# untitled.net
KiCad netlist of a schematic drawn in EAGLE
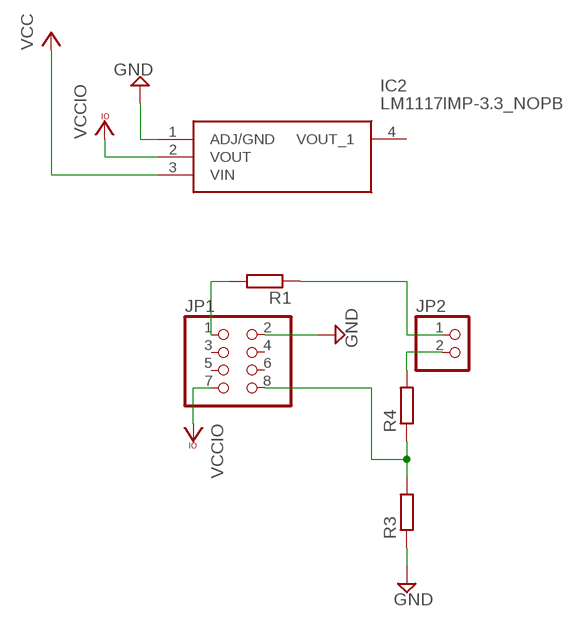
[diagram p0: schematic, sheet 1]

(export (version "E")
  (design (tool "Eeschema 10.0.6"))
  (components
    (comp (ref "IC2")
      (value "LM1117IMP-3.3_NOPB")
      (footprint "eagle-import:SOT230P700X180-4N")
      (fields
        (field (name "MANUFACTURER_PART_NUMBER") "LM1117IMP-3.3/NOPB")
        (field (name "MOUSER_PART_NUMBER") "926-LM1117IMP3.3NOPB")
        (field (name "RS_PART_NUMBER") "1977198")
      )
      (libsource (lib "eagle-import") (part "LM1117IMP-3.3_NOPB"))
    )
    (comp (ref "JP1")
      (value "PINHD-2X4")
      (footprint "eagle-import:2X04")
      (libsource (lib "eagle-import") (part "PINHD-2X4"))
    )
    (comp (ref "JP2")
      (value "PINHD-1X2")
      (footprint "eagle-import:1X02")
      (libsource (lib "eagle-import") (part "PINHD-1X2"))
    )
    (comp (ref "R1")
      (value "R-EU_M0805")
      (footprint "eagle-import:M0805")
      (libsource (lib "eagle-import") (part "R-EU_M0805"))
    )
    (comp (ref "R3")
      (value "R-EU_M0805")
      (footprint "eagle-import:M0805")
      (libsource (lib "eagle-import") (part "R-EU_M0805"))
    )
    (comp (ref "R4")
      (value "R-EU_M0805")
      (footprint "eagle-import:M0805")
      (libsource (lib "eagle-import") (part "R-EU_M0805"))
    )
  )
  (nets
    (net (code "1") (name "GND") (class "Default")
      (node (ref "IC2") (pin "1") (pinfunction "ADJ/GND_1") (pintype "power_in"))
      (node (ref "JP1") (pin "2") (pinfunction "2_2") (pintype "passive"))
      (node (ref "R3") (pin "1") (pinfunction "1_1") (pintype "passive"))
    )
    (net (code "2") (name "Net-(JP1-Pad1)") (class "Default")
      (node (ref "JP1") (pin "1") (pinfunction "1_1") (pintype "passive"))
      (node (ref "R1") (pin "2") (pinfunction "2_2") (pintype "passive"))
    )
    (net (code "3") (name "Net-(JP1-Pad8)") (class "Default")
      (node (ref "JP1") (pin "8") (pinfunction "8_8") (pintype "passive"))
      (node (ref "R3") (pin "2") (pinfunction "2_2") (pintype "passive"))
      (node (ref "R4") (pin "1") (pinfunction "1_1") (pintype "passive"))
    )
    (net (code "4") (name "Net-(JP2-Pad1)") (class "Default")
      (node (ref "JP2") (pin "1") (pinfunction "1_1") (pintype "passive"))
      (node (ref "R1") (pin "1") (pinfunction "1_1") (pintype "passive"))
    )
    (net (code "5") (name "Net-(JP2-Pad2)") (class "Default")
      (node (ref "JP2") (pin "2") (pinfunction "2_2") (pintype "passive"))
      (node (ref "R4") (pin "2") (pinfunction "2_2") (pintype "passive"))
    )
    (net (code "6") (name "VCC") (class "Default")
      (node (ref "IC2") (pin "3") (pinfunction "VIN_3") (pintype "input"))
    )
    (net (code "7") (name "VCCIO") (class "Default")
      (node (ref "IC2") (pin "2") (pinfunction "VOUT_2") (pintype "output"))
      (node (ref "JP1") (pin "7") (pinfunction "7_7") (pintype "passive"))
    )
    (net (code "8") (name "unconnected-(IC2-VOUT_1-Pad4)") (class "Default")
      (node (ref "IC2") (pin "4") (pinfunction "VOUT_1_4") (pintype "output"))
    )
    (net (code "9") (name "unconnected-(JP1-Pad3)") (class "Default")
      (node (ref "JP1") (pin "3") (pinfunction "3_3") (pintype "passive"))
    )
    (net (code "10") (name "unconnected-(JP1-Pad4)") (class "Default")
      (node (ref "JP1") (pin "4") (pinfunction "4_4") (pintype "passive"))
    )
    (net (code "11") (name "unconnected-(JP1-Pad5)") (class "Default")
      (node (ref "JP1") (pin "5") (pinfunction "5_5") (pintype "passive"))
    )
    (net (code "12") (name "unconnected-(JP1-Pad6)") (class "Default")
      (node (ref "JP1") (pin "6") (pinfunction "6_6") (pintype "passive"))
    )
  )
)
